# hypernode.net
KiCad netlist of a schematic drawn in EAGLE
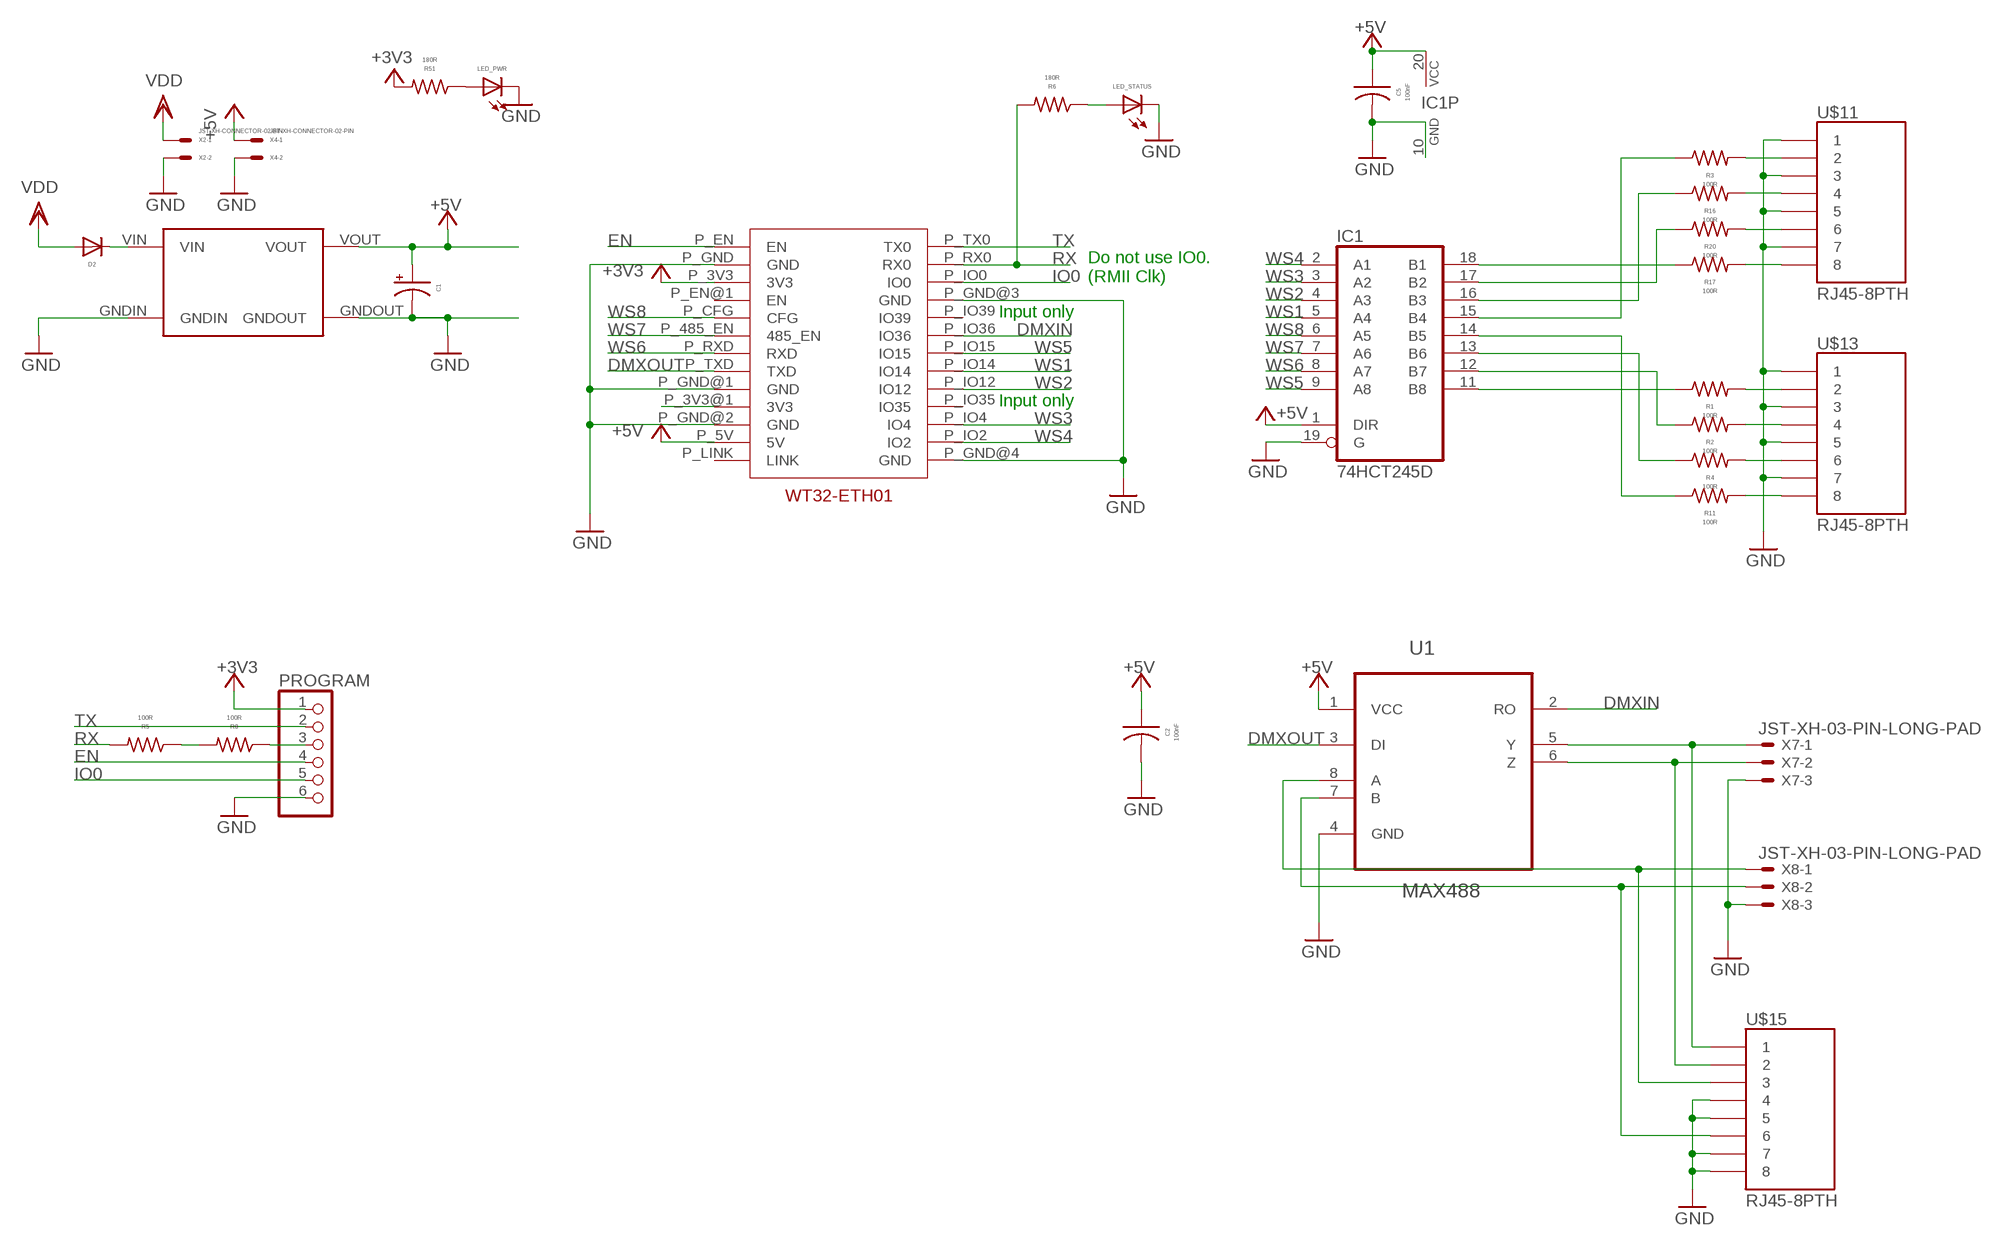
[diagram p0: schematic, sheet 1]

(export (version "E")
  (design (tool "Eeschema 10.0.6"))
  (components
    (comp (ref "C1")
      (value "CAPACITOR_SMC-D")
      (footprint "eagle-import:RCL_SMC_D")
      (libsource (lib "eagle-import") (part "CAPACITOR_SMC-D"))
    )
    (comp (ref "C2")
      (value "100nF")
      (footprint "eagle-import:ADAFRUIT_C0603")
      (libsource (lib "eagle-import") (part "CAPACITOR_0603"))
    )
    (comp (ref "C5")
      (value "100nF")
      (footprint "eagle-import:ADAFRUIT_C0603")
      (libsource (lib "eagle-import") (part "CAPACITOR_0603"))
    )
    (comp (ref "D2")
      (value "DIODE_SMB")
      (footprint "eagle-import:DIODE_SMB")
      (libsource (lib "eagle-import") (part "DIODE_SMB"))
    )
    (comp (ref "IC1")
      (value "74HCT245D")
      (footprint "eagle-import:SO20W")
      (fields (field (name "SPICEPREFIX") "X"))
      (libsource (lib "eagle-import") (part "74245DWAC"))
    )
    (comp (ref "LED_PWR")
      (value "LED0603")
      (footprint "eagle-import:ADAFRUIT_CHIPLED_0603")
      (libsource (lib "eagle-import") (part "LED0603"))
    )
    (comp (ref "LED_STATUS")
      (value "LED0603")
      (footprint "eagle-import:ADAFRUIT_CHIPLED_0603")
      (libsource (lib "eagle-import") (part "LED0603"))
    )
    (comp (ref "PROGRAM")
      (value "PINHD-1X6")
      (footprint "eagle-import:1X06")
      (libsource (lib "eagle-import") (part "PINHD-1X6"))
    )
    (comp (ref "R1")
      (value "100R")
      (footprint "eagle-import:ADAFRUIT_R0603")
      (libsource (lib "eagle-import") (part "RESISTOR"))
    )
    (comp (ref "R2")
      (value "100R")
      (footprint "eagle-import:ADAFRUIT_R0603")
      (libsource (lib "eagle-import") (part "RESISTOR"))
    )
    (comp (ref "R3")
      (value "100R")
      (footprint "eagle-import:ADAFRUIT_R0603")
      (libsource (lib "eagle-import") (part "RESISTOR"))
    )
    (comp (ref "R4")
      (value "100R")
      (footprint "eagle-import:ADAFRUIT_R0603")
      (libsource (lib "eagle-import") (part "RESISTOR"))
    )
    (comp (ref "R5")
      (value "100R")
      (footprint "eagle-import:ADAFRUIT_R0603")
      (libsource (lib "eagle-import") (part "RESISTOR"))
    )
    (comp (ref "R6")
      (value "180R")
      (footprint "eagle-import:ADAFRUIT_R0603")
      (libsource (lib "eagle-import") (part "RESISTOR"))
    )
    (comp (ref "R8")
      (value "100R")
      (footprint "eagle-import:ADAFRUIT_R0603")
      (libsource (lib "eagle-import") (part "RESISTOR"))
    )
    (comp (ref "R11")
      (value "100R")
      (footprint "eagle-import:ADAFRUIT_R0603")
      (libsource (lib "eagle-import") (part "RESISTOR"))
    )
    (comp (ref "R16")
      (value "100R")
      (footprint "eagle-import:ADAFRUIT_R0603")
      (libsource (lib "eagle-import") (part "RESISTOR"))
    )
    (comp (ref "R17")
      (value "100R")
      (footprint "eagle-import:ADAFRUIT_R0603")
      (libsource (lib "eagle-import") (part "RESISTOR"))
    )
    (comp (ref "R20")
      (value "100R")
      (footprint "eagle-import:ADAFRUIT_R0603")
      (libsource (lib "eagle-import") (part "RESISTOR"))
    )
    (comp (ref "R51")
      (value "180R")
      (footprint "eagle-import:ADAFRUIT_R0603")
      (libsource (lib "eagle-import") (part "RESISTOR"))
    )
    (comp (ref "U$3")
      (value "STEPDOWNMODULE")
      (footprint "eagle-import:STEPDOWN_MODULE")
      (libsource (lib "eagle-import") (part "STEPDOWNMODULE"))
    )
    (comp (ref "U$11")
      (value "RJ45-8PTH")
      (footprint "eagle-import:RJ45-8")
      (libsource (lib "eagle-import") (part "RJ45-8PTH"))
    )
    (comp (ref "U$13")
      (value "RJ45-8PTH")
      (footprint "eagle-import:RJ45-8")
      (libsource (lib "eagle-import") (part "RJ45-8PTH"))
    )
    (comp (ref "U$15")
      (value "RJ45-8PTH")
      (footprint "eagle-import:RJ45-8")
      (libsource (lib "eagle-import") (part "RJ45-8PTH"))
    )
    (comp (ref "U$17")
      (value "WT32-ETH01WT32-ETH01-SMD")
      (footprint "eagle-import:WT32-ETH01-SMD")
      (libsource (lib "eagle-import") (part "WT32-ETH01WT32-ETH01-SMD"))
    )
    (comp (ref "U1")
      (value "MAX488")
      (footprint "eagle-import:SOIC127P600X175-8N")
      (fields (field (name "MPN") "MAX488CSA+"))
      (libsource (lib "eagle-import") (part "MAX488CSA+"))
    )
    (comp (ref "X2")
      (value "JST-XH-CONNECTOR-02-PIN")
      (footprint "eagle-import:REMBRANDT-ELECTRONICS---JST-XH-CONNECTORS-V1-0_JST-XH-02-PACKAGE-LONG-PAD")
      (libsource (lib "eagle-import") (part "JST-XH-CONNECTOR-02-PIN"))
    )
    (comp (ref "X4")
      (value "JST-XH-CONNECTOR-02-PIN")
      (footprint "eagle-import:REMBRANDT-ELECTRONICS---JST-XH-CONNECTORS-V1-0_JST-XH-02-PACKAGE-LONG-PAD")
      (libsource (lib "eagle-import") (part "JST-XH-CONNECTOR-02-PIN"))
    )
    (comp (ref "X7")
      (value "JST-XH-03-PIN-LONG-PAD")
      (footprint "eagle-import:JST-XH-03-PACKAGE-LONG-PAD")
      (libsource (lib "eagle-import") (part "JST-XH-03-PIN-LONG-PAD"))
    )
    (comp (ref "X8")
      (value "JST-XH-03-PIN-LONG-PAD")
      (footprint "eagle-import:JST-XH-03-PACKAGE-LONG-PAD")
      (libsource (lib "eagle-import") (part "JST-XH-03-PIN-LONG-PAD"))
    )
  )
  (nets
    (net (code "1") (name "+3V3") (class "Default")
      (node (ref "PROGRAM") (pin "1") (pinfunction "1_1") (pintype "passive"))
      (node (ref "R51") (pin "2") (pinfunction "2_2") (pintype "passive"))
      (node (ref "U$17") (pin "P_3V3") (pinfunction "3V3_P_3V3") (pintype "bidirectional"))
    )
    (net (code "2") (name "+5V") (class "Default")
      (node (ref "C1") (pin "+") (pinfunction "+_+") (pintype "passive"))
      (node (ref "C2") (pin "1") (pinfunction "1_1") (pintype "passive"))
      (node (ref "C5") (pin "1") (pinfunction "1_1") (pintype "passive"))
      (node (ref "IC1") (pin "1") (pinfunction "DIR_1") (pintype "input"))
      (node (ref "IC1") (pin "20") (pinfunction "VCC_20") (pintype "power_in"))
      (node (ref "U$17") (pin "P_5V") (pinfunction "5V_P_5V") (pintype "bidirectional"))
      (node (ref "U$3") (pin "VOUT") (pinfunction "VOUT_VOUT") (pintype "bidirectional"))
      (node (ref "U1") (pin "1") (pinfunction "VCC_1") (pintype "power_in"))
      (node (ref "X4") (pin "1") (pinfunction "S_1") (pintype "passive"))
    )
    (net (code "3") (name "/DMXIN") (class "Default")
      (node (ref "U$17") (pin "P_IO36") (pinfunction "IO36_P_IO36") (pintype "bidirectional"))
      (node (ref "U1") (pin "2") (pinfunction "RO_2") (pintype "output"))
    )
    (net (code "4") (name "/DMXOUT") (class "Default")
      (node (ref "U$17") (pin "P_TXD") (pinfunction "TXD_P_TXD") (pintype "bidirectional"))
      (node (ref "U1") (pin "3") (pinfunction "DI_3") (pintype "input"))
    )
    (net (code "5") (name "/EN") (class "Default")
      (node (ref "PROGRAM") (pin "4") (pinfunction "4_4") (pintype "passive"))
      (node (ref "U$17") (pin "P_EN") (pinfunction "EN_P_EN") (pintype "bidirectional"))
    )
    (net (code "6") (name "/IO0") (class "Default")
      (node (ref "PROGRAM") (pin "5") (pinfunction "5_5") (pintype "passive"))
      (node (ref "U$17") (pin "P_IO0") (pinfunction "IO0_P_IO0") (pintype "bidirectional"))
    )
    (net (code "7") (name "/RX") (class "Default")
      (node (ref "R5") (pin "2") (pinfunction "2_2") (pintype "passive"))
      (node (ref "R6") (pin "2") (pinfunction "2_2") (pintype "passive"))
      (node (ref "U$17") (pin "P_RX0") (pinfunction "RX0_P_RX0") (pintype "bidirectional"))
    )
    (net (code "8") (name "/TX") (class "Default")
      (node (ref "PROGRAM") (pin "2") (pinfunction "2_2") (pintype "passive"))
      (node (ref "U$17") (pin "P_TX0") (pinfunction "TX0_P_TX0") (pintype "bidirectional"))
    )
    (net (code "9") (name "/WS1") (class "Default")
      (node (ref "IC1") (pin "5") (pinfunction "A4_5") (pintype "bidirectional"))
      (node (ref "U$17") (pin "P_IO14") (pinfunction "IO14_P_IO14") (pintype "bidirectional"))
    )
    (net (code "10") (name "/WS2") (class "Default")
      (node (ref "IC1") (pin "4") (pinfunction "A3_4") (pintype "bidirectional"))
      (node (ref "U$17") (pin "P_IO12") (pinfunction "IO12_P_IO12") (pintype "bidirectional"))
    )
    (net (code "11") (name "/WS3") (class "Default")
      (node (ref "IC1") (pin "3") (pinfunction "A2_3") (pintype "bidirectional"))
      (node (ref "U$17") (pin "P_IO4") (pinfunction "IO4_P_IO4") (pintype "bidirectional"))
    )
    (net (code "12") (name "/WS4") (class "Default")
      (node (ref "IC1") (pin "2") (pinfunction "A1_2") (pintype "bidirectional"))
      (node (ref "U$17") (pin "P_IO2") (pinfunction "IO2_P_IO2") (pintype "bidirectional"))
    )
    (net (code "13") (name "/WS5") (class "Default")
      (node (ref "IC1") (pin "9") (pinfunction "A8_9") (pintype "bidirectional"))
      (node (ref "U$17") (pin "P_IO15") (pinfunction "IO15_P_IO15") (pintype "bidirectional"))
    )
    (net (code "14") (name "/WS6") (class "Default")
      (node (ref "IC1") (pin "8") (pinfunction "A7_8") (pintype "bidirectional"))
      (node (ref "U$17") (pin "P_RXD") (pinfunction "RXD_P_RXD") (pintype "bidirectional"))
    )
    (net (code "15") (name "/WS7") (class "Default")
      (node (ref "IC1") (pin "7") (pinfunction "A6_7") (pintype "bidirectional"))
      (node (ref "U$17") (pin "P_485_EN") (pinfunction "485_EN_P_485_EN") (pintype "bidirectional"))
    )
    (net (code "16") (name "/WS8") (class "Default")
      (node (ref "IC1") (pin "6") (pinfunction "A5_6") (pintype "bidirectional"))
      (node (ref "U$17") (pin "P_CFG") (pinfunction "CFG_P_CFG") (pintype "bidirectional"))
    )
    (net (code "17") (name "GND") (class "Default")
      (node (ref "C1") (pin "-") (pinfunction "-_-") (pintype "passive"))
      (node (ref "C2") (pin "2") (pinfunction "2_2") (pintype "passive"))
      (node (ref "C5") (pin "2") (pinfunction "2_2") (pintype "passive"))
      (node (ref "IC1") (pin "10") (pinfunction "GND_10") (pintype "power_in"))
      (node (ref "IC1") (pin "19") (pinfunction "G_19") (pintype "input"))
      (node (ref "LED_PWR") (pin "C") (pinfunction "C_C") (pintype "passive"))
      (node (ref "LED_STATUS") (pin "C") (pinfunction "C_C") (pintype "passive"))
      (node (ref "PROGRAM") (pin "6") (pinfunction "6_6") (pintype "passive"))
      (node (ref "U$11") (pin "1") (pinfunction "1_1") (pintype "bidirectional"))
      (node (ref "U$11") (pin "3") (pinfunction "3_3") (pintype "bidirectional"))
      (node (ref "U$11") (pin "5") (pinfunction "5_5") (pintype "bidirectional"))
      (node (ref "U$11") (pin "7") (pinfunction "7_7") (pintype "bidirectional"))
      (node (ref "U$13") (pin "1") (pinfunction "1_1") (pintype "bidirectional"))
      (node (ref "U$13") (pin "3") (pinfunction "3_3") (pintype "bidirectional"))
      (node (ref "U$13") (pin "5") (pinfunction "5_5") (pintype "bidirectional"))
      (node (ref "U$13") (pin "7") (pinfunction "7_7") (pintype "bidirectional"))
      (node (ref "U$15") (pin "4") (pinfunction "4_4") (pintype "bidirectional"))
      (node (ref "U$15") (pin "5") (pinfunction "5_5") (pintype "bidirectional"))
      (node (ref "U$15") (pin "7") (pinfunction "7_7") (pintype "bidirectional"))
      (node (ref "U$15") (pin "8") (pinfunction "8_8") (pintype "bidirectional"))
      (node (ref "U$17") (pin "P_GND") (pinfunction "GND_P_GND") (pintype "bidirectional"))
      (node (ref "U$17") (pin "P_GND@1") (pinfunction "GND_P_GND@1") (pintype "bidirectional"))
      (node (ref "U$17") (pin "P_GND@2") (pinfunction "GND_P_GND@2") (pintype "bidirectional"))
      (node (ref "U$17") (pin "P_GND@3") (pinfunction "GND_P_GND@3") (pintype "bidirectional"))
      (node (ref "U$17") (pin "P_GND@4") (pinfunction "GND_P_GND@4") (pintype "bidirectional"))
      (node (ref "U$3") (pin "GNDIN") (pinfunction "GNDIN_GNDIN") (pintype "bidirectional"))
      (node (ref "U$3") (pin "GNDOUT") (pinfunction "GNDOUT_GNDOUT") (pintype "bidirectional"))
      (node (ref "U1") (pin "4") (pinfunction "GND_4") (pintype "passive"))
      (node (ref "X2") (pin "2") (pinfunction "S_2") (pintype "passive"))
      (node (ref "X4") (pin "2") (pinfunction "S_2") (pintype "passive"))
      (node (ref "X7") (pin "3") (pinfunction "S_3") (pintype "passive"))
      (node (ref "X8") (pin "3") (pinfunction "S_3") (pintype "passive"))
    )
    (net (code "18") (name "Net-(D2-PadC)") (class "Default")
      (node (ref "D2") (pin "C") (pinfunction "C_C") (pintype "passive"))
      (node (ref "U$3") (pin "VIN") (pinfunction "VIN_VIN") (pintype "bidirectional"))
    )
    (net (code "19") (name "Net-(IC1A-B1)") (class "Default")
      (node (ref "IC1") (pin "18") (pinfunction "B1_18") (pintype "bidirectional"))
      (node (ref "R17") (pin "1") (pinfunction "1_1") (pintype "passive"))
    )
    (net (code "20") (name "Net-(IC1A-B2)") (class "Default")
      (node (ref "IC1") (pin "17") (pinfunction "B2_17") (pintype "bidirectional"))
      (node (ref "R20") (pin "1") (pinfunction "1_1") (pintype "passive"))
    )
    (net (code "21") (name "Net-(IC1A-B3)") (class "Default")
      (node (ref "IC1") (pin "16") (pinfunction "B3_16") (pintype "bidirectional"))
      (node (ref "R16") (pin "1") (pinfunction "1_1") (pintype "passive"))
    )
    (net (code "22") (name "Net-(IC1A-B4)") (class "Default")
      (node (ref "IC1") (pin "15") (pinfunction "B4_15") (pintype "bidirectional"))
      (node (ref "R3") (pin "1") (pinfunction "1_1") (pintype "passive"))
    )
    (net (code "23") (name "Net-(IC1A-B5)") (class "Default")
      (node (ref "IC1") (pin "14") (pinfunction "B5_14") (pintype "bidirectional"))
      (node (ref "R11") (pin "1") (pinfunction "1_1") (pintype "passive"))
    )
    (net (code "24") (name "Net-(IC1A-B6)") (class "Default")
      (node (ref "IC1") (pin "13") (pinfunction "B6_13") (pintype "bidirectional"))
      (node (ref "R4") (pin "1") (pinfunction "1_1") (pintype "passive"))
    )
    (net (code "25") (name "Net-(IC1A-B7)") (class "Default")
      (node (ref "IC1") (pin "12") (pinfunction "B7_12") (pintype "bidirectional"))
      (node (ref "R2") (pin "1") (pinfunction "1_1") (pintype "passive"))
    )
    (net (code "26") (name "Net-(IC1A-B8)") (class "Default")
      (node (ref "IC1") (pin "11") (pinfunction "B8_11") (pintype "bidirectional"))
      (node (ref "R1") (pin "1") (pinfunction "1_1") (pintype "passive"))
    )
    (net (code "27") (name "Net-(LED_PWR-PadA)") (class "Default")
      (node (ref "LED_PWR") (pin "A") (pinfunction "A_A") (pintype "passive"))
      (node (ref "R51") (pin "1") (pinfunction "1_1") (pintype "passive"))
    )
    (net (code "28") (name "Net-(LED_STATUS-PadA)") (class "Default")
      (node (ref "LED_STATUS") (pin "A") (pinfunction "A_A") (pintype "passive"))
      (node (ref "R6") (pin "1") (pinfunction "1_1") (pintype "passive"))
    )
    (net (code "29") (name "Net-(PROGRAM-Pad3)") (class "Default")
      (node (ref "PROGRAM") (pin "3") (pinfunction "3_3") (pintype "passive"))
      (node (ref "R8") (pin "1") (pinfunction "1_1") (pintype "passive"))
    )
    (net (code "30") (name "Net-(R1-Pad2)") (class "Default")
      (node (ref "R1") (pin "2") (pinfunction "2_2") (pintype "passive"))
      (node (ref "U$13") (pin "2") (pinfunction "2_2") (pintype "bidirectional"))
    )
    (net (code "31") (name "Net-(R2-Pad2)") (class "Default")
      (node (ref "R2") (pin "2") (pinfunction "2_2") (pintype "passive"))
      (node (ref "U$13") (pin "4") (pinfunction "4_4") (pintype "bidirectional"))
    )
    (net (code "32") (name "Net-(R3-Pad2)") (class "Default")
      (node (ref "R3") (pin "2") (pinfunction "2_2") (pintype "passive"))
      (node (ref "U$11") (pin "2") (pinfunction "2_2") (pintype "bidirectional"))
    )
    (net (code "33") (name "Net-(R4-Pad2)") (class "Default")
      (node (ref "R4") (pin "2") (pinfunction "2_2") (pintype "passive"))
      (node (ref "U$13") (pin "6") (pinfunction "6_6") (pintype "bidirectional"))
    )
    (net (code "34") (name "Net-(R5-Pad1)") (class "Default")
      (node (ref "R5") (pin "1") (pinfunction "1_1") (pintype "passive"))
      (node (ref "R8") (pin "2") (pinfunction "2_2") (pintype "passive"))
    )
    (net (code "35") (name "Net-(R11-Pad2)") (class "Default")
      (node (ref "R11") (pin "2") (pinfunction "2_2") (pintype "passive"))
      (node (ref "U$13") (pin "8") (pinfunction "8_8") (pintype "bidirectional"))
    )
    (net (code "36") (name "Net-(R16-Pad2)") (class "Default")
      (node (ref "R16") (pin "2") (pinfunction "2_2") (pintype "passive"))
      (node (ref "U$11") (pin "4") (pinfunction "4_4") (pintype "bidirectional"))
    )
    (net (code "37") (name "Net-(R17-Pad2)") (class "Default")
      (node (ref "R17") (pin "2") (pinfunction "2_2") (pintype "passive"))
      (node (ref "U$11") (pin "8") (pinfunction "8_8") (pintype "bidirectional"))
    )
    (net (code "38") (name "Net-(R20-Pad2)") (class "Default")
      (node (ref "R20") (pin "2") (pinfunction "2_2") (pintype "passive"))
      (node (ref "U$11") (pin "6") (pinfunction "6_6") (pintype "bidirectional"))
    )
    (net (code "39") (name "Net-(U1-A)") (class "Default")
      (node (ref "U$15") (pin "3") (pinfunction "3_3") (pintype "bidirectional"))
      (node (ref "U1") (pin "8") (pinfunction "A_8") (pintype "input"))
      (node (ref "X8") (pin "1") (pinfunction "S_1") (pintype "passive"))
    )
    (net (code "40") (name "Net-(U1-B)") (class "Default")
      (node (ref "U$15") (pin "6") (pinfunction "6_6") (pintype "bidirectional"))
      (node (ref "U1") (pin "7") (pinfunction "B_7") (pintype "input"))
      (node (ref "X8") (pin "2") (pinfunction "S_2") (pintype "passive"))
    )
    (net (code "41") (name "Net-(U1-Y)") (class "Default")
      (node (ref "U$15") (pin "1") (pinfunction "1_1") (pintype "bidirectional"))
      (node (ref "U1") (pin "5") (pinfunction "Y_5") (pintype "output"))
      (node (ref "X7") (pin "1") (pinfunction "S_1") (pintype "passive"))
    )
    (net (code "42") (name "Net-(U1-Z)") (class "Default")
      (node (ref "U$15") (pin "2") (pinfunction "2_2") (pintype "bidirectional"))
      (node (ref "U1") (pin "6") (pinfunction "Z_6") (pintype "output"))
      (node (ref "X7") (pin "2") (pinfunction "S_2") (pintype "passive"))
    )
    (net (code "43") (name "VDD") (class "Default")
      (node (ref "D2") (pin "A") (pinfunction "A_A") (pintype "passive"))
      (node (ref "X2") (pin "1") (pinfunction "S_1") (pintype "passive"))
    )
    (net (code "44") (name "unconnected-(U$17-3V3-PadP_3V3@1)") (class "Default")
      (node (ref "U$17") (pin "P_3V3@1") (pinfunction "3V3_P_3V3@1") (pintype "bidirectional"))
    )
    (net (code "45") (name "unconnected-(U$17-EN-PadP_EN@1)") (class "Default")
      (node (ref "U$17") (pin "P_EN@1") (pinfunction "EN_P_EN@1") (pintype "bidirectional"))
    )
    (net (code "46") (name "unconnected-(U$17-IO35-PadP_IO35)") (class "Default")
      (node (ref "U$17") (pin "P_IO35") (pinfunction "IO35_P_IO35") (pintype "bidirectional"))
    )
    (net (code "47") (name "unconnected-(U$17-IO39-PadP_IO39)") (class "Default")
      (node (ref "U$17") (pin "P_IO39") (pinfunction "IO39_P_IO39") (pintype "bidirectional"))
    )
    (net (code "48") (name "unconnected-(U$17-LINK-PadP_LINK)") (class "Default")
      (node (ref "U$17") (pin "P_LINK") (pinfunction "LINK_P_LINK") (pintype "bidirectional"))
    )
  )
)
